# rpi.net
KiCad netlist of a schematic drawn in EAGLE
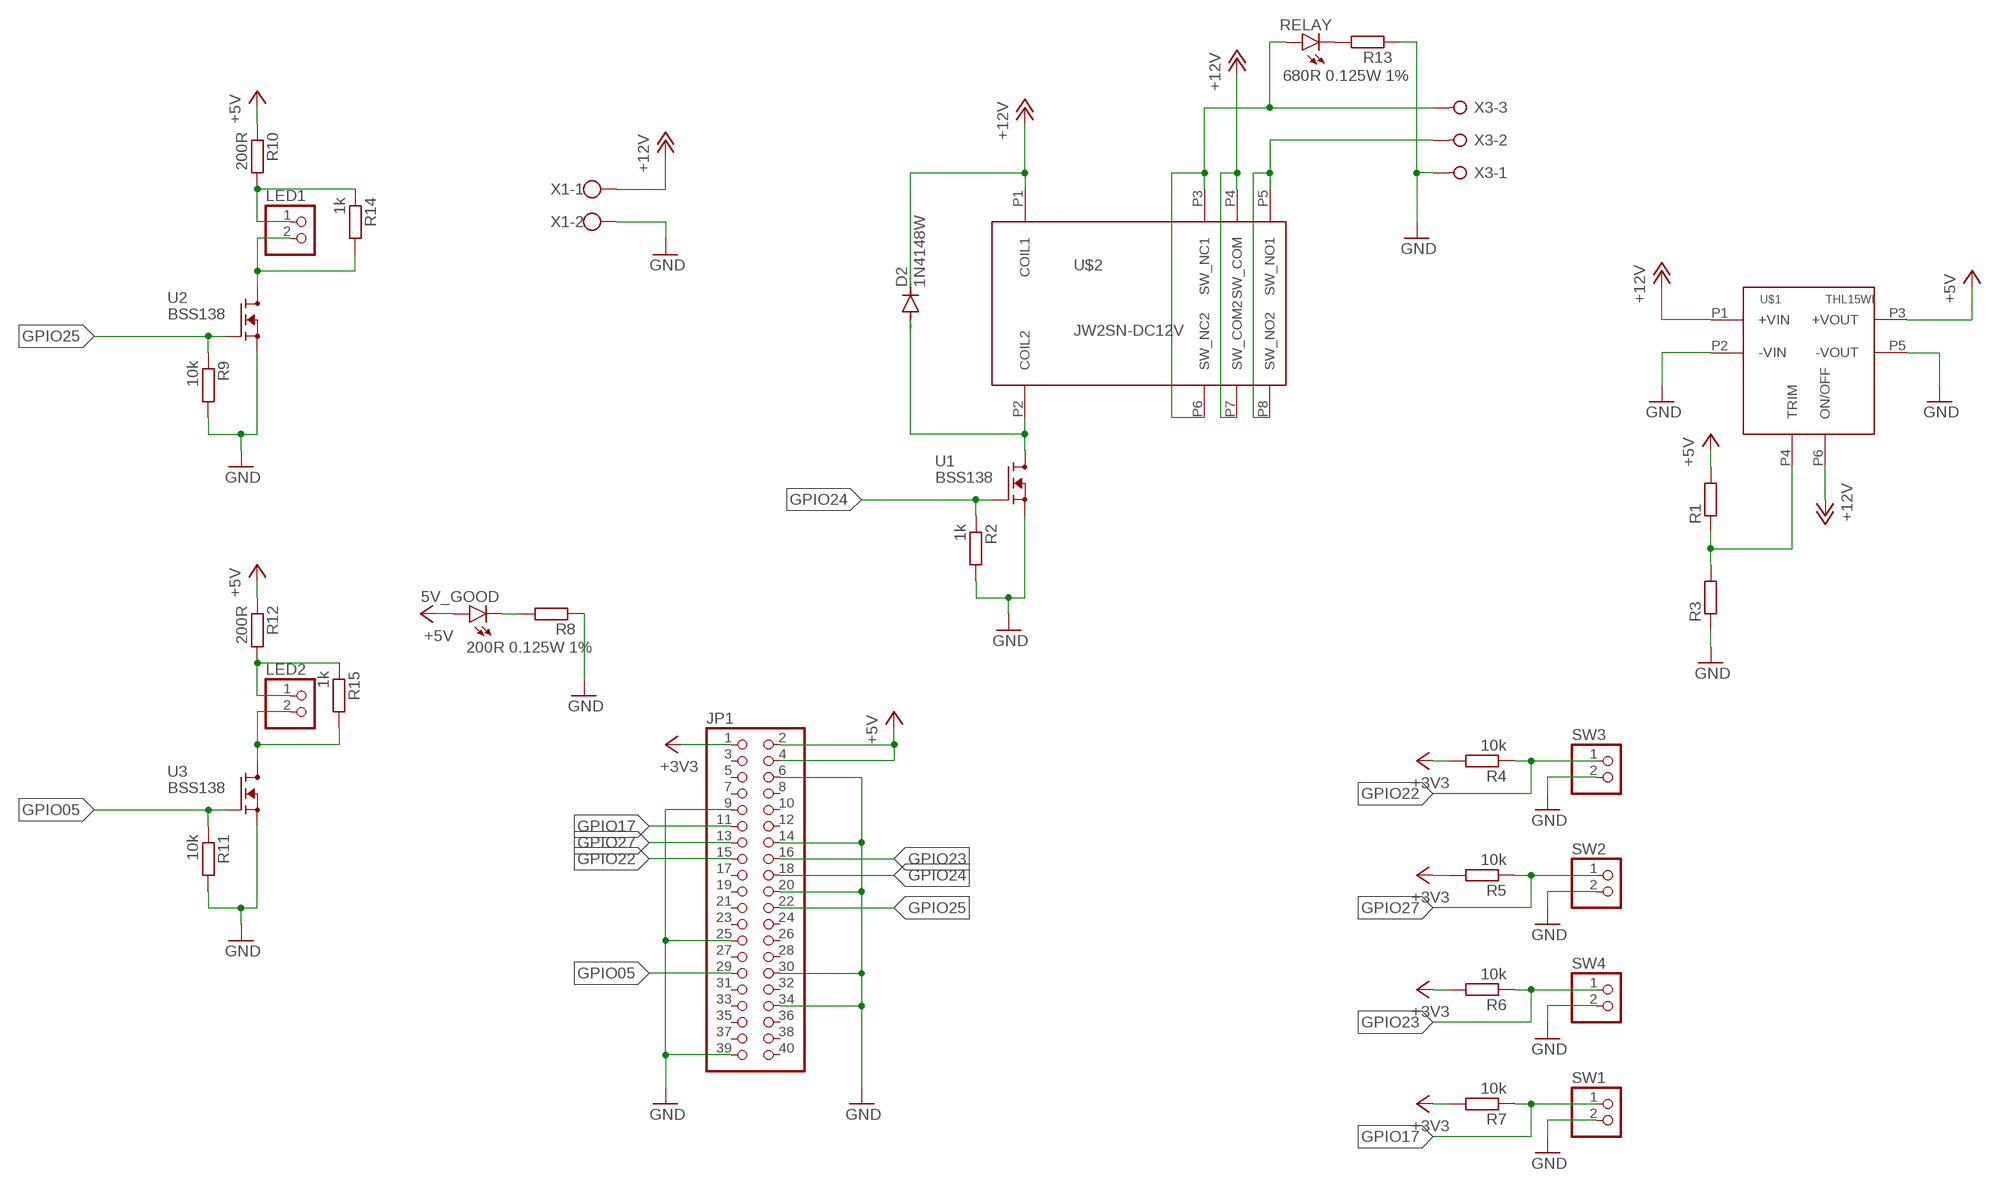
[diagram p0: schematic, sheet 1]

(export (version "E")
  (design (tool "Eeschema 10.0.6"))
  (components
    (comp (ref "5V_GOOD")
      (value "LEDCHIPLED_0805")
      (footprint "eagle-import:CHIPLED_0805")
      (libsource (lib "eagle-import") (part "LEDCHIPLED_0805"))
    )
    (comp (ref "D2")
      (value "1N4148W")
      (footprint "eagle-import:SOD-123_MINI-SMA")
      (libsource (lib "eagle-import") (part "CGRM400-G1"))
    )
    (comp (ref "JP1")
      (value "PINHD-2X20")
      (footprint "eagle-import:2X20")
      (libsource (lib "eagle-import") (part "PINHD-2X20"))
    )
    (comp (ref "LED1")
      (value "PINHD-1X2")
      (footprint "eagle-import:1X02")
      (libsource (lib "eagle-import") (part "PINHD-1X2"))
    )
    (comp (ref "LED2")
      (value "PINHD-1X2")
      (footprint "eagle-import:1X02")
      (libsource (lib "eagle-import") (part "PINHD-1X2"))
    )
    (comp (ref "R1")
      (value "R-EU_R0805")
      (footprint "eagle-import:R0805")
      (libsource (lib "eagle-import") (part "R-EU_R0805"))
    )
    (comp (ref "R2")
      (value "1k")
      (footprint "eagle-import:R0805")
      (libsource (lib "eagle-import") (part "R-EU_R0805"))
    )
    (comp (ref "R3")
      (value "R-EU_R0805")
      (footprint "eagle-import:R0805")
      (libsource (lib "eagle-import") (part "R-EU_R0805"))
    )
    (comp (ref "R4")
      (value "10k")
      (footprint "eagle-import:R0805")
      (libsource (lib "eagle-import") (part "R-EU_R0805"))
    )
    (comp (ref "R5")
      (value "10k")
      (footprint "eagle-import:R0805")
      (libsource (lib "eagle-import") (part "R-EU_R0805"))
    )
    (comp (ref "R6")
      (value "10k")
      (footprint "eagle-import:R0805")
      (libsource (lib "eagle-import") (part "R-EU_R0805"))
    )
    (comp (ref "R7")
      (value "10k")
      (footprint "eagle-import:R0805")
      (libsource (lib "eagle-import") (part "R-EU_R0805"))
    )
    (comp (ref "R8")
      (value "200R 0.125W 1%")
      (footprint "eagle-import:R0805")
      (libsource (lib "eagle-import") (part "resistor_348_R-EU_R0805"))
    )
    (comp (ref "R9")
      (value "10k")
      (footprint "eagle-import:R0805")
      (libsource (lib "eagle-import") (part "R-EU_R0805"))
    )
    (comp (ref "R10")
      (value "200R")
      (footprint "eagle-import:R0805")
      (libsource (lib "eagle-import") (part "R-EU_R0805"))
    )
    (comp (ref "R11")
      (value "10k")
      (footprint "eagle-import:R0805")
      (libsource (lib "eagle-import") (part "R-EU_R0805"))
    )
    (comp (ref "R12")
      (value "200R")
      (footprint "eagle-import:R0805")
      (libsource (lib "eagle-import") (part "R-EU_R0805"))
    )
    (comp (ref "R13")
      (value "680R 0.125W 1%")
      (footprint "eagle-import:R0805")
      (libsource (lib "eagle-import") (part "resistor_348_R-EU_R0805"))
    )
    (comp (ref "R14")
      (value "1k")
      (footprint "eagle-import:R0805")
      (libsource (lib "eagle-import") (part "R-EU_R0805"))
    )
    (comp (ref "R15")
      (value "1k")
      (footprint "eagle-import:R0805")
      (libsource (lib "eagle-import") (part "R-EU_R0805"))
    )
    (comp (ref "RELAY")
      (value "LEDCHIPLED_0805")
      (footprint "eagle-import:CHIPLED_0805")
      (libsource (lib "eagle-import") (part "LEDCHIPLED_0805"))
    )
    (comp (ref "SW1")
      (value "PINHD-1X2")
      (footprint "eagle-import:1X02")
      (libsource (lib "eagle-import") (part "PINHD-1X2"))
    )
    (comp (ref "SW2")
      (value "PINHD-1X2")
      (footprint "eagle-import:1X02")
      (libsource (lib "eagle-import") (part "PINHD-1X2"))
    )
    (comp (ref "SW3")
      (value "PINHD-1X2")
      (footprint "eagle-import:1X02")
      (libsource (lib "eagle-import") (part "PINHD-1X2"))
    )
    (comp (ref "SW4")
      (value "PINHD-1X2")
      (footprint "eagle-import:1X02")
      (libsource (lib "eagle-import") (part "PINHD-1X2"))
    )
    (comp (ref "U$1")
      (value "THL15WI")
      (footprint "eagle-import:THL15WI")
      (libsource (lib "eagle-import") (part "THL15WI"))
    )
    (comp (ref "U$2")
      (value "JW2SN-DC12V")
      (footprint "eagle-import:JW2FORMC")
      (libsource (lib "eagle-import") (part "JW2SN-DC12V"))
    )
    (comp (ref "U1")
      (value "BSS138")
      (footprint "eagle-import:SOT23")
      (libsource (lib "eagle-import") (part "BSS138"))
    )
    (comp (ref "U2")
      (value "BSS138")
      (footprint "eagle-import:SOT23")
      (libsource (lib "eagle-import") (part "BSS138"))
    )
    (comp (ref "U3")
      (value "BSS138")
      (footprint "eagle-import:SOT23")
      (libsource (lib "eagle-import") (part "BSS138"))
    )
    (comp (ref "X1")
      (value "W237-102")
      (footprint "eagle-import:W237-102")
      (fields (field (name "MPN") "237-102"))
      (libsource (lib "eagle-import") (part "W237-102"))
    )
    (comp (ref "X3")
      (value "W237-3E")
      (footprint "eagle-import:W237-3E")
      (libsource (lib "eagle-import") (part "W237-3E"))
    )
  )
  (nets
    (net (code "1") (name "+3V3") (class "Default")
      (node (ref "JP1") (pin "1") (pinfunction "1_1") (pintype "passive"))
      (node (ref "R4") (pin "2") (pinfunction "2_2") (pintype "passive"))
      (node (ref "R5") (pin "2") (pinfunction "2_2") (pintype "passive"))
      (node (ref "R6") (pin "2") (pinfunction "2_2") (pintype "passive"))
      (node (ref "R7") (pin "2") (pinfunction "2_2") (pintype "passive"))
    )
    (net (code "2") (name "+5V") (class "Default")
      (node (ref "5V_GOOD") (pin "A") (pinfunction "A_A") (pintype "passive"))
      (node (ref "JP1") (pin "2") (pinfunction "2_2") (pintype "passive"))
      (node (ref "JP1") (pin "4") (pinfunction "4_4") (pintype "passive"))
      (node (ref "R1") (pin "2") (pinfunction "2_2") (pintype "passive"))
      (node (ref "R10") (pin "1") (pinfunction "1_1") (pintype "passive"))
      (node (ref "R12") (pin "1") (pinfunction "1_1") (pintype "passive"))
      (node (ref "U$1") (pin "P3") (pinfunction "+VOUT_P3") (pintype "bidirectional"))
    )
    (net (code "3") (name "+12V") (class "Default")
      (node (ref "D2") (pin "C") (pinfunction "C_C") (pintype "passive"))
      (node (ref "U$1") (pin "P1") (pinfunction "+VIN_P1") (pintype "bidirectional"))
      (node (ref "U$1") (pin "P6") (pinfunction "ON/OFF_P6") (pintype "bidirectional"))
      (node (ref "U$2") (pin "P1") (pinfunction "COIL1_P1") (pintype "bidirectional"))
      (node (ref "U$2") (pin "P4") (pinfunction "SW_COM_P4") (pintype "bidirectional"))
      (node (ref "U$2") (pin "P7") (pinfunction "SW_COM2_P7") (pintype "bidirectional"))
      (node (ref "X1") (pin "1") (pinfunction "KL_1") (pintype "passive"))
    )
    (net (code "4") (name "GND") (class "Default")
      (node (ref "JP1") (pin "14") (pinfunction "14_14") (pintype "passive"))
      (node (ref "JP1") (pin "20") (pinfunction "20_20") (pintype "passive"))
      (node (ref "JP1") (pin "25") (pinfunction "25_25") (pintype "passive"))
      (node (ref "JP1") (pin "30") (pinfunction "30_30") (pintype "passive"))
      (node (ref "JP1") (pin "34") (pinfunction "34_34") (pintype "passive"))
      (node (ref "JP1") (pin "39") (pinfunction "39_39") (pintype "passive"))
      (node (ref "JP1") (pin "6") (pinfunction "6_6") (pintype "passive"))
      (node (ref "JP1") (pin "9") (pinfunction "9_9") (pintype "passive"))
      (node (ref "R11") (pin "2") (pinfunction "2_2") (pintype "passive"))
      (node (ref "R13") (pin "1") (pinfunction "1_1") (pintype "passive"))
      (node (ref "R2") (pin "2") (pinfunction "2_2") (pintype "passive"))
      (node (ref "R3") (pin "1") (pinfunction "1_1") (pintype "passive"))
      (node (ref "R8") (pin "1") (pinfunction "1_1") (pintype "passive"))
      (node (ref "R9") (pin "2") (pinfunction "2_2") (pintype "passive"))
      (node (ref "SW1") (pin "2") (pinfunction "2_2") (pintype "passive"))
      (node (ref "SW2") (pin "2") (pinfunction "2_2") (pintype "passive"))
      (node (ref "SW3") (pin "2") (pinfunction "2_2") (pintype "passive"))
      (node (ref "SW4") (pin "2") (pinfunction "2_2") (pintype "passive"))
      (node (ref "U$1") (pin "P2") (pinfunction "-VIN_P2") (pintype "bidirectional"))
      (node (ref "U$1") (pin "P5") (pinfunction "-VOUT_P5") (pintype "bidirectional"))
      (node (ref "U1") (pin "2") (pinfunction "S_2") (pintype "passive"))
      (node (ref "U2") (pin "2") (pinfunction "S_2") (pintype "passive"))
      (node (ref "U3") (pin "2") (pinfunction "S_2") (pintype "passive"))
      (node (ref "X1") (pin "2") (pinfunction "KL_2") (pintype "passive"))
      (node (ref "X3") (pin "1") (pinfunction "KL_1") (pintype "passive"))
    )
    (net (code "5") (name "GPIO05") (class "Default")
      (node (ref "JP1") (pin "29") (pinfunction "29_29") (pintype "passive"))
      (node (ref "R11") (pin "1") (pinfunction "1_1") (pintype "passive"))
      (node (ref "U3") (pin "1") (pinfunction "G_1") (pintype "passive"))
    )
    (net (code "6") (name "GPIO17") (class "Default")
      (node (ref "JP1") (pin "11") (pinfunction "11_11") (pintype "passive"))
      (node (ref "R7") (pin "1") (pinfunction "1_1") (pintype "passive"))
      (node (ref "SW1") (pin "1") (pinfunction "1_1") (pintype "passive"))
    )
    (net (code "7") (name "GPIO22") (class "Default")
      (node (ref "JP1") (pin "15") (pinfunction "15_15") (pintype "passive"))
      (node (ref "R4") (pin "1") (pinfunction "1_1") (pintype "passive"))
      (node (ref "SW3") (pin "1") (pinfunction "1_1") (pintype "passive"))
    )
    (net (code "8") (name "GPIO23") (class "Default")
      (node (ref "JP1") (pin "16") (pinfunction "16_16") (pintype "passive"))
      (node (ref "R6") (pin "1") (pinfunction "1_1") (pintype "passive"))
      (node (ref "SW4") (pin "1") (pinfunction "1_1") (pintype "passive"))
    )
    (net (code "9") (name "GPIO24") (class "Default")
      (node (ref "JP1") (pin "18") (pinfunction "18_18") (pintype "passive"))
      (node (ref "R2") (pin "1") (pinfunction "1_1") (pintype "passive"))
      (node (ref "U1") (pin "1") (pinfunction "G_1") (pintype "passive"))
    )
    (net (code "10") (name "GPIO25") (class "Default")
      (node (ref "JP1") (pin "22") (pinfunction "22_22") (pintype "passive"))
      (node (ref "R9") (pin "1") (pinfunction "1_1") (pintype "passive"))
      (node (ref "U2") (pin "1") (pinfunction "G_1") (pintype "passive"))
    )
    (net (code "11") (name "GPIO27") (class "Default")
      (node (ref "JP1") (pin "13") (pinfunction "13_13") (pintype "passive"))
      (node (ref "R5") (pin "1") (pinfunction "1_1") (pintype "passive"))
      (node (ref "SW2") (pin "1") (pinfunction "1_1") (pintype "passive"))
    )
    (net (code "12") (name "Net-(5V_GOOD-PadC)") (class "Default")
      (node (ref "5V_GOOD") (pin "C") (pinfunction "C_C") (pintype "passive"))
      (node (ref "R8") (pin "2") (pinfunction "2_2") (pintype "passive"))
    )
    (net (code "13") (name "Net-(LED1-Pad1)") (class "Default")
      (node (ref "LED1") (pin "1") (pinfunction "1_1") (pintype "passive"))
      (node (ref "R10") (pin "2") (pinfunction "2_2") (pintype "passive"))
      (node (ref "R14") (pin "1") (pinfunction "1_1") (pintype "passive"))
    )
    (net (code "14") (name "Net-(LED2-Pad1)") (class "Default")
      (node (ref "LED2") (pin "1") (pinfunction "1_1") (pintype "passive"))
      (node (ref "R12") (pin "2") (pinfunction "2_2") (pintype "passive"))
      (node (ref "R15") (pin "1") (pinfunction "1_1") (pintype "passive"))
    )
    (net (code "15") (name "Net-(R13-Pad2)") (class "Default")
      (node (ref "R13") (pin "2") (pinfunction "2_2") (pintype "passive"))
      (node (ref "RELAY") (pin "C") (pinfunction "C_C") (pintype "passive"))
    )
    (net (code "16") (name "Net-(U$1-TRIM)") (class "Default")
      (node (ref "R1") (pin "1") (pinfunction "1_1") (pintype "passive"))
      (node (ref "R3") (pin "2") (pinfunction "2_2") (pintype "passive"))
      (node (ref "U$1") (pin "P4") (pinfunction "TRIM_P4") (pintype "bidirectional"))
    )
    (net (code "17") (name "Net-(U$2-COIL2)") (class "Default")
      (node (ref "D2") (pin "A") (pinfunction "A_A") (pintype "passive"))
      (node (ref "U$2") (pin "P2") (pinfunction "COIL2_P2") (pintype "bidirectional"))
      (node (ref "U1") (pin "3") (pinfunction "D_3") (pintype "passive"))
    )
    (net (code "18") (name "Net-(U$2-SW_NC1)") (class "Default")
      (node (ref "RELAY") (pin "A") (pinfunction "A_A") (pintype "passive"))
      (node (ref "U$2") (pin "P3") (pinfunction "SW_NC1_P3") (pintype "bidirectional"))
      (node (ref "U$2") (pin "P6") (pinfunction "SW_NC2_P6") (pintype "bidirectional"))
      (node (ref "X3") (pin "3") (pinfunction "KL_3") (pintype "passive"))
    )
    (net (code "19") (name "Net-(U$2-SW_NO1)") (class "Default")
      (node (ref "U$2") (pin "P5") (pinfunction "SW_NO1_P5") (pintype "bidirectional"))
      (node (ref "U$2") (pin "P8") (pinfunction "SW_NO2_P8") (pintype "bidirectional"))
      (node (ref "X3") (pin "2") (pinfunction "KL_2") (pintype "passive"))
    )
    (net (code "20") (name "Net-(U2-D)") (class "Default")
      (node (ref "LED1") (pin "2") (pinfunction "2_2") (pintype "passive"))
      (node (ref "R14") (pin "2") (pinfunction "2_2") (pintype "passive"))
      (node (ref "U2") (pin "3") (pinfunction "D_3") (pintype "passive"))
    )
    (net (code "21") (name "Net-(U3-D)") (class "Default")
      (node (ref "LED2") (pin "2") (pinfunction "2_2") (pintype "passive"))
      (node (ref "R15") (pin "2") (pinfunction "2_2") (pintype "passive"))
      (node (ref "U3") (pin "3") (pinfunction "D_3") (pintype "passive"))
    )
    (net (code "22") (name "unconnected-(JP1-Pad3)") (class "Default")
      (node (ref "JP1") (pin "3") (pinfunction "3_3") (pintype "passive"))
    )
    (net (code "23") (name "unconnected-(JP1-Pad5)") (class "Default")
      (node (ref "JP1") (pin "5") (pinfunction "5_5") (pintype "passive"))
    )
    (net (code "24") (name "unconnected-(JP1-Pad7)") (class "Default")
      (node (ref "JP1") (pin "7") (pinfunction "7_7") (pintype "passive"))
    )
    (net (code "25") (name "unconnected-(JP1-Pad8)") (class "Default")
      (node (ref "JP1") (pin "8") (pinfunction "8_8") (pintype "passive"))
    )
    (net (code "26") (name "unconnected-(JP1-Pad10)") (class "Default")
      (node (ref "JP1") (pin "10") (pinfunction "10_10") (pintype "passive"))
    )
    (net (code "27") (name "unconnected-(JP1-Pad12)") (class "Default")
      (node (ref "JP1") (pin "12") (pinfunction "12_12") (pintype "passive"))
    )
    (net (code "28") (name "unconnected-(JP1-Pad17)") (class "Default")
      (node (ref "JP1") (pin "17") (pinfunction "17_17") (pintype "passive"))
    )
    (net (code "29") (name "unconnected-(JP1-Pad19)") (class "Default")
      (node (ref "JP1") (pin "19") (pinfunction "19_19") (pintype "passive"))
    )
    (net (code "30") (name "unconnected-(JP1-Pad21)") (class "Default")
      (node (ref "JP1") (pin "21") (pinfunction "21_21") (pintype "passive"))
    )
    (net (code "31") (name "unconnected-(JP1-Pad23)") (class "Default")
      (node (ref "JP1") (pin "23") (pinfunction "23_23") (pintype "passive"))
    )
    (net (code "32") (name "unconnected-(JP1-Pad24)") (class "Default")
      (node (ref "JP1") (pin "24") (pinfunction "24_24") (pintype "passive"))
    )
    (net (code "33") (name "unconnected-(JP1-Pad26)") (class "Default")
      (node (ref "JP1") (pin "26") (pinfunction "26_26") (pintype "passive"))
    )
    (net (code "34") (name "unconnected-(JP1-Pad27)") (class "Default")
      (node (ref "JP1") (pin "27") (pinfunction "27_27") (pintype "passive"))
    )
    (net (code "35") (name "unconnected-(JP1-Pad28)") (class "Default")
      (node (ref "JP1") (pin "28") (pinfunction "28_28") (pintype "passive"))
    )
    (net (code "36") (name "unconnected-(JP1-Pad31)") (class "Default")
      (node (ref "JP1") (pin "31") (pinfunction "31_31") (pintype "passive"))
    )
    (net (code "37") (name "unconnected-(JP1-Pad32)") (class "Default")
      (node (ref "JP1") (pin "32") (pinfunction "32_32") (pintype "passive"))
    )
    (net (code "38") (name "unconnected-(JP1-Pad33)") (class "Default")
      (node (ref "JP1") (pin "33") (pinfunction "33_33") (pintype "passive"))
    )
    (net (code "39") (name "unconnected-(JP1-Pad35)") (class "Default")
      (node (ref "JP1") (pin "35") (pinfunction "35_35") (pintype "passive"))
    )
    (net (code "40") (name "unconnected-(JP1-Pad36)") (class "Default")
      (node (ref "JP1") (pin "36") (pinfunction "36_36") (pintype "passive"))
    )
    (net (code "41") (name "unconnected-(JP1-Pad37)") (class "Default")
      (node (ref "JP1") (pin "37") (pinfunction "37_37") (pintype "passive"))
    )
    (net (code "42") (name "unconnected-(JP1-Pad38)") (class "Default")
      (node (ref "JP1") (pin "38") (pinfunction "38_38") (pintype "passive"))
    )
    (net (code "43") (name "unconnected-(JP1-Pad40)") (class "Default")
      (node (ref "JP1") (pin "40") (pinfunction "40_40") (pintype "passive"))
    )
  )
)
